# 60V_Detector.net
KiCad netlist of a schematic drawn in Altium Designer
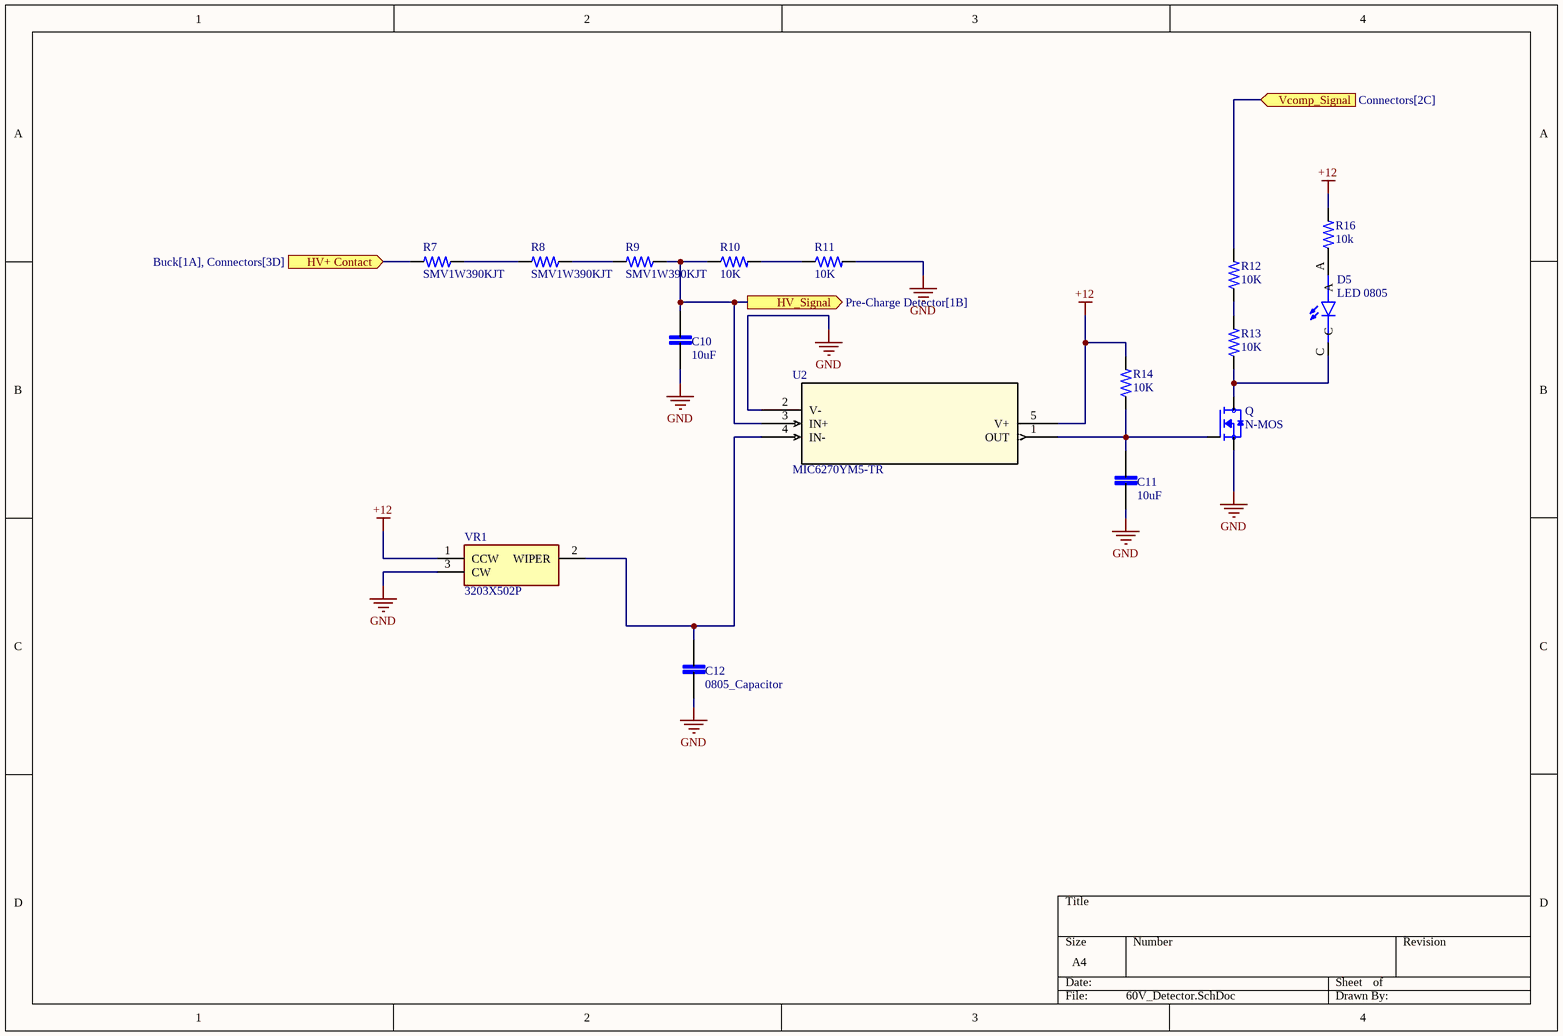
[diagram p0: 60V_Detector.SchDoc]

(export (version "E")
  (design (tool "Eeschema 10.0.6"))
  (components
    (comp (ref "C10")
      (value "10uF")
      (footprint "0805")
      (fields (field (name "MP") "LD051A121KAB2A") (field (name "MF") "AVX"))
      (libsource (lib "Capacitors SMD") (part "0805_Capacitor"))
    )
    (comp (ref "C11")
      (value "10uF")
      (footprint "0805")
      (fields (field (name "MP") "LD051A121KAB2A") (field (name "MF") "AVX"))
      (libsource (lib "Capacitors SMD") (part "0805_Capacitor"))
    )
    (comp (ref "C12")
      (value "0805_Capacitor")
      (footprint "0805")
      (fields (field (name "MP") "LD051A121KAB2A") (field (name "MF") "AVX"))
      (libsource (lib "Capacitors SMD") (part "0805_Capacitor"))
    )
    (comp (ref "D5")
      (value "LED 0805")
      (footprint "LED 0805")
      (description "LED Uni-Color Green 4-Pin Chip 0805 T/R")
      (fields (field (name "MP") "597-3305-607F"))
      (libsource (lib "LEDs SMD") (part "LED 0805"))
    )
    (comp (ref "Q")
      (value "N-MOS")
      (footprint "AO3402")
      (description "D-PAK")
      (fields (field (name "MP") "AO3402") (field (name "MF") "Alpha &"))
      (libsource (lib "Mosfet SMD") (part "N-MOS"))
    )
    (comp (ref "R7")
      (value "SMV1W390KJT")
      (footprint "SMV1W390KJT")
      (fields
        (field (name "MP") "2-2176053-0")
        (field (name "TOLERANCE") "1%")
        (field (name "MF") "TE Connectivity")
      )
      (libsource (lib "Resistors SMD") (part "SMV1W390KJT"))
    )
    (comp (ref "R8")
      (value "SMV1W390KJT")
      (footprint "SMV1W390KJT")
      (fields
        (field (name "MP") "2-2176053-0")
        (field (name "TOLERANCE") "1%")
        (field (name "MF") "TE Connectivity")
      )
      (libsource (lib "Resistors SMD") (part "SMV1W390KJT"))
    )
    (comp (ref "R9")
      (value "SMV1W390KJT")
      (footprint "SMV1W390KJT")
      (fields
        (field (name "MP") "2-2176053-0")
        (field (name "TOLERANCE") "1%")
        (field (name "MF") "TE Connectivity")
      )
      (libsource (lib "Resistors SMD") (part "SMV1W390KJT"))
    )
    (comp (ref "R10")
      (value "10K")
      (footprint "0805")
      (fields
        (field (name "MP") "2-2176053-0")
        (field (name "TOLERANCE") "1%")
        (field (name "MF") "TE Connectivity")
      )
      (libsource (lib "Resistors SMD") (part "0805_Resistor"))
    )
    (comp (ref "R11")
      (value "10K")
      (footprint "0805")
      (fields
        (field (name "MP") "2-2176053-0")
        (field (name "TOLERANCE") "1%")
        (field (name "MF") "TE Connectivity")
      )
      (libsource (lib "Resistors SMD") (part "0805_Resistor"))
    )
    (comp (ref "R12")
      (value "10K")
      (footprint "0805")
      (fields
        (field (name "MP") "2-2176053-0")
        (field (name "TOLERANCE") "1%")
        (field (name "MF") "TE Connectivity")
      )
      (libsource (lib "Resistors SMD") (part "0805_Resistor"))
    )
    (comp (ref "R13")
      (value "10K")
      (footprint "0805")
      (fields
        (field (name "MP") "2-2176053-0")
        (field (name "TOLERANCE") "1%")
        (field (name "MF") "TE Connectivity")
      )
      (libsource (lib "Resistors SMD") (part "0805_Resistor"))
    )
    (comp (ref "R14")
      (value "10K")
      (footprint "0805")
      (fields
        (field (name "MP") "2-2176053-0")
        (field (name "TOLERANCE") "1%")
        (field (name "MF") "TE Connectivity")
      )
      (libsource (lib "Resistors SMD") (part "0805_Resistor"))
    )
    (comp (ref "R16")
      (value "10k")
      (footprint "0805")
      (fields
        (field (name "MP") "2-2176053-0")
        (field (name "TOLERANCE") "1%")
        (field (name "MF") "TE Connectivity")
      )
      (libsource (lib "SMD_Generic") (part "0805_Resistor"))
    )
    (comp (ref "U2")
      (value "MIC6270YM5-TR")
      (footprint "MIC6270")
      (description "No Description Available")
      (fields (field (name "COPYRIGHT") "Copyright (C) 2024 Ultra Librarian. All rights reserved."))
      (libsource (lib "Comparators Chip SMD") (part "MIC6270YM5-TR"))
    )
    (comp (ref "VR1")
      (value "3203X502P")
      (footprint "SamacSys:3203X502P")
      (description "Variable Resistor")
      (fields (field (name "MOUSER PART NUMBER") "279-3203X502P"))
      (libsource (lib "*") (part "3203X502P"))
    )
  )
  (nets
    (net (code "1") (name "+12") (class "Default")
      (node (ref "R14") (pin "2") (pinfunction "2_2") (pintype "passive"))
      (node (ref "R16") (pin "2") (pinfunction "2_2") (pintype "passive"))
      (node (ref "U2") (pin "5") (pinfunction "V+_5") (pintype "power_in"))
      (node (ref "VR1") (pin "1") (pinfunction "CCW_1") (pintype "passive"))
    )
    (net (code "2") (name "/HV+ Contact") (class "Default")
      (node (ref "R7") (pin "2") (pinfunction "2_2") (pintype "passive"))
    )
    (net (code "3") (name "/HV_Signal") (class "Default")
      (node (ref "C10") (pin "2") (pinfunction "2_2") (pintype "passive"))
      (node (ref "R10") (pin "1") (pinfunction "1_1") (pintype "passive"))
      (node (ref "R9") (pin "1") (pinfunction "1_1") (pintype "passive"))
      (node (ref "U2") (pin "3") (pinfunction "IN+_3") (pintype "input"))
    )
    (net (code "4") (name "/Vcomp_Signal") (class "Default")
      (node (ref "R12") (pin "2") (pinfunction "2_2") (pintype "passive"))
    )
    (net (code "5") (name "GND") (class "Default")
      (node (ref "C10") (pin "1") (pinfunction "1_1") (pintype "passive"))
      (node (ref "C11") (pin "1") (pinfunction "1_1") (pintype "passive"))
      (node (ref "C12") (pin "1") (pinfunction "1_1") (pintype "passive"))
      (node (ref "Q") (pin "2") (pinfunction "S_2") (pintype "passive"))
      (node (ref "R11") (pin "2") (pinfunction "2_2") (pintype "passive"))
      (node (ref "U2") (pin "2") (pinfunction "V-_2") (pintype "power_in"))
      (node (ref "VR1") (pin "3") (pinfunction "CW_3") (pintype "passive"))
    )
    (net (code "6") (name "Net-(D5-PadA)") (class "Default")
      (node (ref "D5") (pin "A") (pinfunction "A_A") (pintype "passive"))
      (node (ref "R16") (pin "1") (pinfunction "1_1") (pintype "passive"))
    )
    (net (code "7") (name "Net-(Q-D)") (class "Default")
      (node (ref "D5") (pin "C") (pinfunction "C_C") (pintype "passive"))
      (node (ref "Q") (pin "3") (pinfunction "D_3") (pintype "passive"))
      (node (ref "R13") (pin "1") (pinfunction "1_1") (pintype "passive"))
    )
    (net (code "8") (name "Net-(Q-G)") (class "Default")
      (node (ref "C11") (pin "2") (pinfunction "2_2") (pintype "passive"))
      (node (ref "Q") (pin "1") (pinfunction "G_1") (pintype "passive"))
      (node (ref "R14") (pin "1") (pinfunction "1_1") (pintype "passive"))
      (node (ref "U2") (pin "1") (pinfunction "OUT_1") (pintype "output"))
    )
    (net (code "9") (name "Net-(R7-Pad1)") (class "Default")
      (node (ref "R7") (pin "1") (pinfunction "1_1") (pintype "passive"))
      (node (ref "R8") (pin "2") (pinfunction "2_2") (pintype "passive"))
    )
    (net (code "10") (name "Net-(R8-Pad1)") (class "Default")
      (node (ref "R8") (pin "1") (pinfunction "1_1") (pintype "passive"))
      (node (ref "R9") (pin "2") (pinfunction "2_2") (pintype "passive"))
    )
    (net (code "11") (name "Net-(R10-Pad2)") (class "Default")
      (node (ref "R10") (pin "2") (pinfunction "2_2") (pintype "passive"))
      (node (ref "R11") (pin "1") (pinfunction "1_1") (pintype "passive"))
    )
    (net (code "12") (name "Net-(R12-Pad1)") (class "Default")
      (node (ref "R12") (pin "1") (pinfunction "1_1") (pintype "passive"))
      (node (ref "R13") (pin "2") (pinfunction "2_2") (pintype "passive"))
    )
    (net (code "13") (name "Net-(U2-IN-)") (class "Default")
      (node (ref "C12") (pin "2") (pinfunction "2_2") (pintype "passive"))
      (node (ref "U2") (pin "4") (pinfunction "IN-_4") (pintype "input"))
      (node (ref "VR1") (pin "2") (pinfunction "WIPER_2") (pintype "passive"))
    )
  )
)
